# P1001-001-007-320_-_Programmer.net
KiCad netlist of a schematic drawn in EAGLE
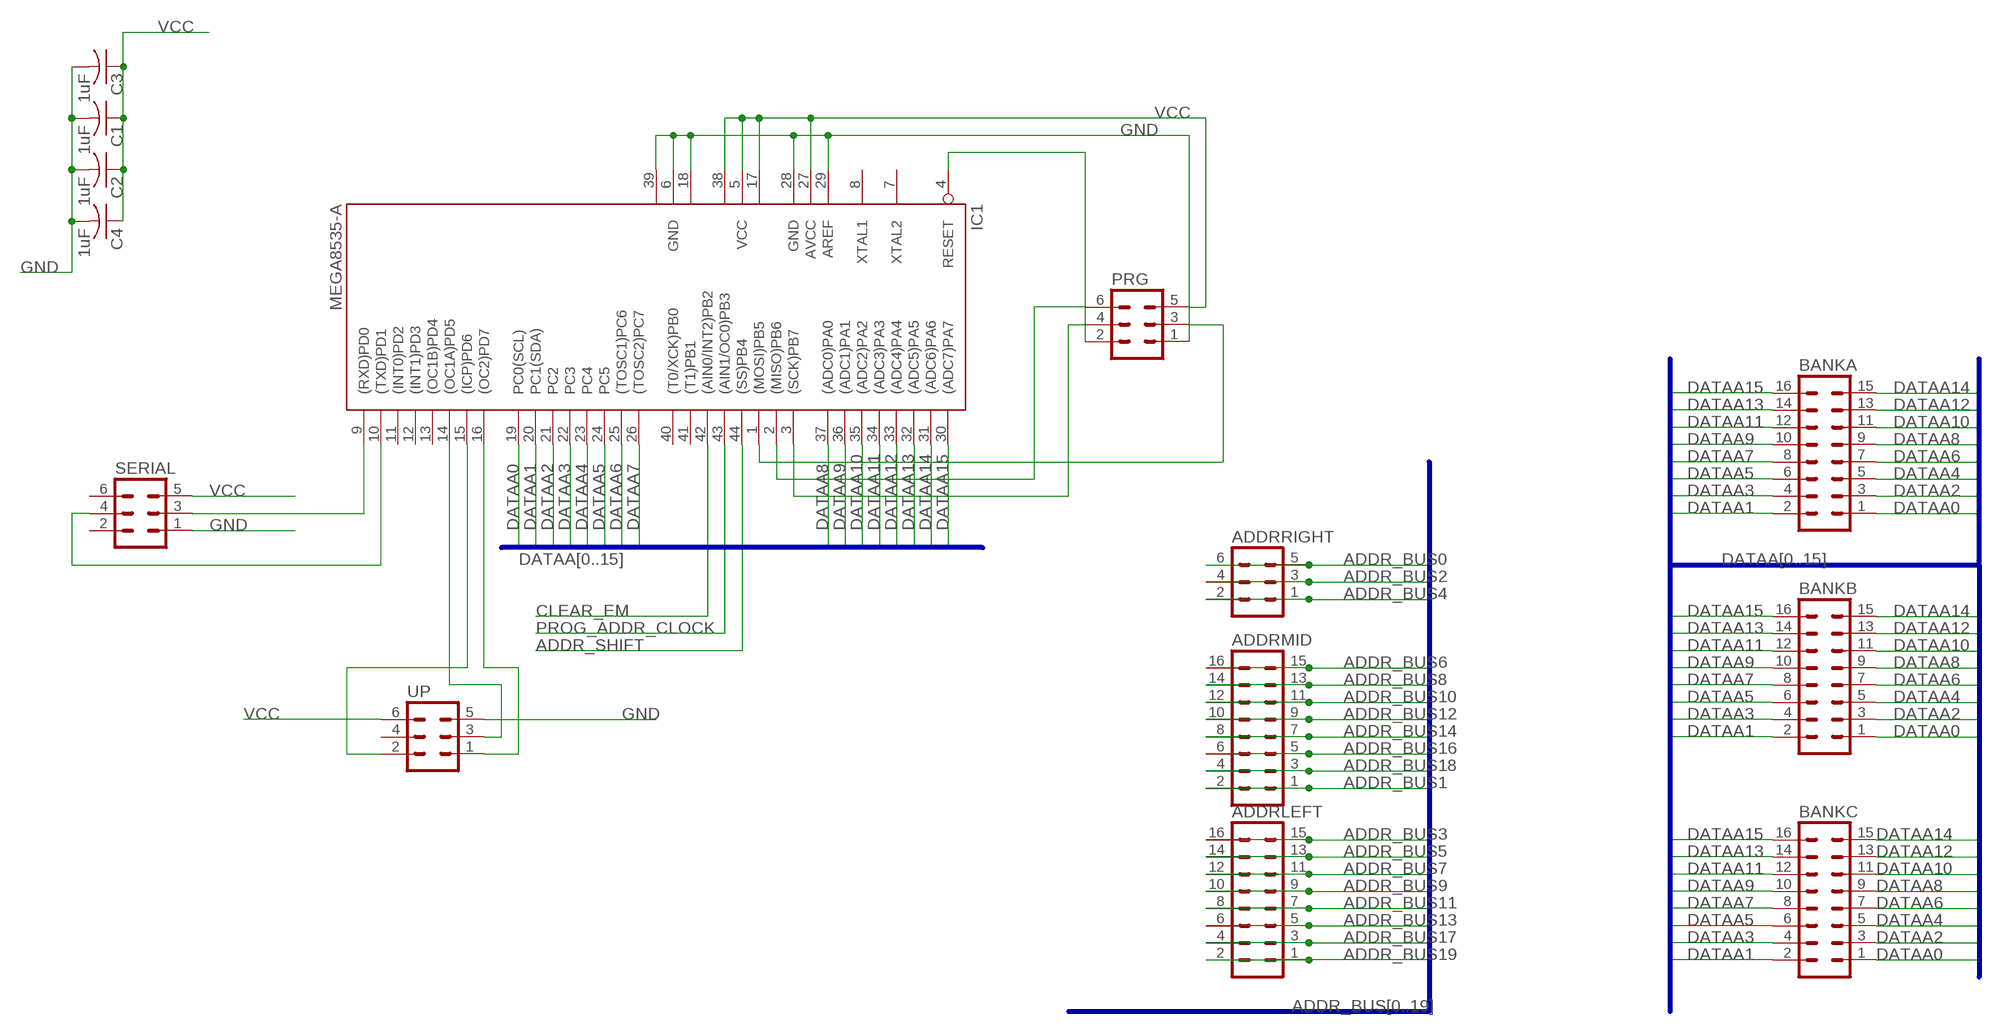
[diagram p0: schematic, sheet 1]
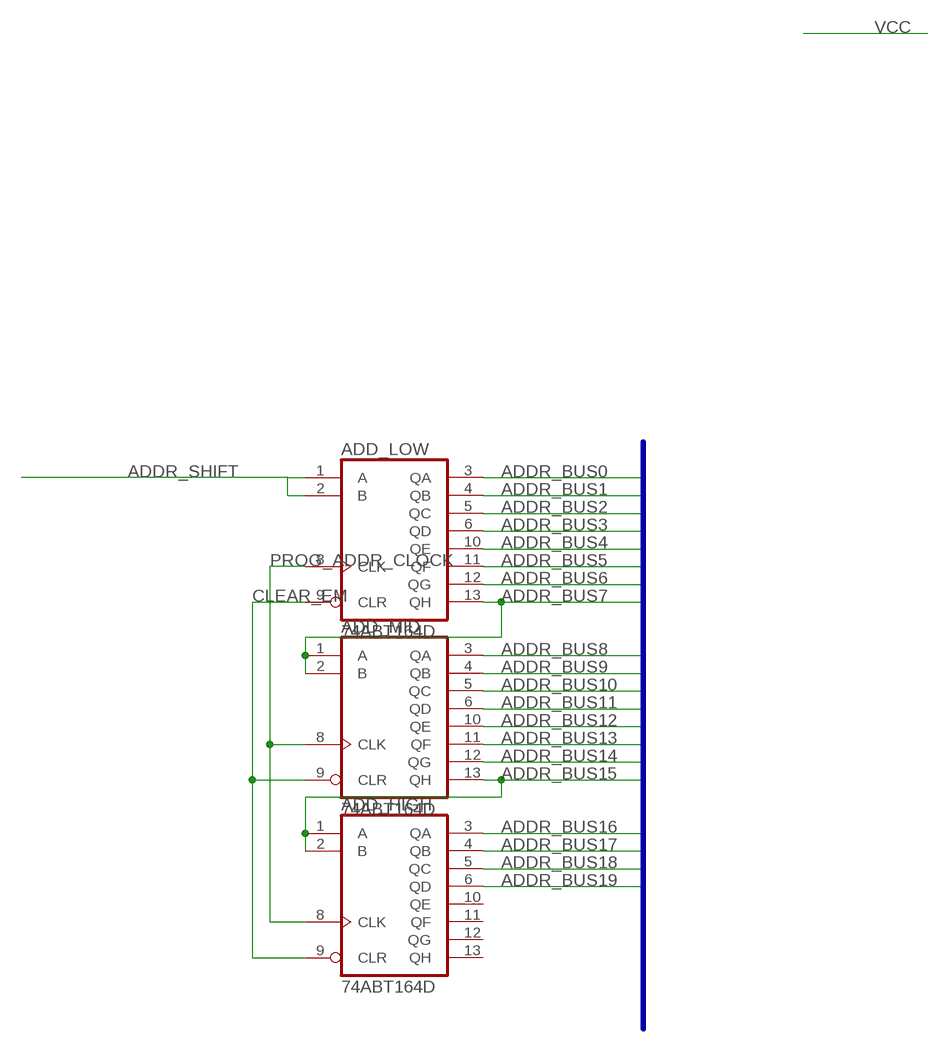
[diagram p1: schematic, sheet 2]

(export (version "E")
  (design (tool "Eeschema 10.0.6"))
  (components
    (comp (ref "ADD_HIGH")
      (value "74ABT164D")
      (footprint "eagle-import:SO14")
      (libsource (lib "eagle-import") (part "74164DABT"))
    )
    (comp (ref "ADD_LOW")
      (value "74ABT164D")
      (footprint "eagle-import:SO14")
      (libsource (lib "eagle-import") (part "74164DABT"))
    )
    (comp (ref "ADD_MID")
      (value "74ABT164D")
      (footprint "eagle-import:SO14")
      (libsource (lib "eagle-import") (part "74164DABT"))
    )
    (comp (ref "ADDRLEFT")
      (value "ML16")
      (footprint "eagle-import:ML16")
      (libsource (lib "eagle-import") (part "ML16"))
    )
    (comp (ref "ADDRMID")
      (value "ML16")
      (footprint "eagle-import:ML16")
      (libsource (lib "eagle-import") (part "ML16"))
    )
    (comp (ref "ADDRRIGHT")
      (value "ML6")
      (footprint "eagle-import:ML6")
      (libsource (lib "eagle-import") (part "ML6"))
    )
    (comp (ref "BANKA")
      (value "ML16")
      (footprint "eagle-import:ML16")
      (libsource (lib "eagle-import") (part "ML16"))
    )
    (comp (ref "BANKB")
      (value "ML16")
      (footprint "eagle-import:ML16")
      (libsource (lib "eagle-import") (part "ML16"))
    )
    (comp (ref "BANKC")
      (value "ML16")
      (footprint "eagle-import:ML16")
      (libsource (lib "eagle-import") (part "ML16"))
    )
    (comp (ref "C1")
      (value "1uF")
      (footprint "eagle-import:C1206")
      (libsource (lib "eagle-import") (part "C-USC1206"))
    )
    (comp (ref "C2")
      (value "1uF")
      (footprint "eagle-import:C1206")
      (libsource (lib "eagle-import") (part "C-USC1206"))
    )
    (comp (ref "C3")
      (value "1uF")
      (footprint "eagle-import:C1206")
      (libsource (lib "eagle-import") (part "C-USC1206"))
    )
    (comp (ref "C4")
      (value "1uF")
      (footprint "eagle-import:C1206")
      (libsource (lib "eagle-import") (part "C-USC1206"))
    )
    (comp (ref "IC1")
      (value "MEGA8535-A")
      (footprint "eagle-import:TQFP44")
      (fields (field (name "MPN") "ATMEGA8535-16AU"))
      (libsource (lib "eagle-import") (part "MEGA8535-A"))
    )
    (comp (ref "PRG")
      (value "ML6")
      (footprint "eagle-import:ML6")
      (libsource (lib "eagle-import") (part "ML6"))
    )
    (comp (ref "SERIAL")
      (value "ML6")
      (footprint "eagle-import:ML6")
      (libsource (lib "eagle-import") (part "ML6"))
    )
    (comp (ref "UP")
      (value "ML6")
      (footprint "eagle-import:ML6")
      (libsource (lib "eagle-import") (part "ML6"))
    )
  )
  (nets
    (net (code "4") (name "ADDR_BUS0") (class "Default")
      (node (ref "ADDRRIGHT") (pin "5") (pinfunction "5_5") (pintype "passive"))
      (node (ref "ADDRRIGHT") (pin "6") (pinfunction "6_6") (pintype "passive"))
      (node (ref "ADD_LOW") (pin "3") (pinfunction "QA_3") (pintype "output"))
    )
    (net (code "5") (name "ADDR_BUS1") (class "Default")
      (node (ref "ADDRMID") (pin "1") (pinfunction "1_1") (pintype "passive"))
      (node (ref "ADDRMID") (pin "2") (pinfunction "2_2") (pintype "passive"))
      (node (ref "ADD_LOW") (pin "4") (pinfunction "QB_4") (pintype "output"))
    )
    (net (code "6") (name "ADDR_BUS2") (class "Default")
      (node (ref "ADDRRIGHT") (pin "3") (pinfunction "3_3") (pintype "passive"))
      (node (ref "ADDRRIGHT") (pin "4") (pinfunction "4_4") (pintype "passive"))
      (node (ref "ADD_LOW") (pin "5") (pinfunction "QC_5") (pintype "output"))
    )
    (net (code "7") (name "ADDR_BUS3") (class "Default")
      (node (ref "ADDRLEFT") (pin "15") (pinfunction "15_15") (pintype "passive"))
      (node (ref "ADDRLEFT") (pin "16") (pinfunction "16_16") (pintype "passive"))
      (node (ref "ADD_LOW") (pin "6") (pinfunction "QD_6") (pintype "output"))
    )
    (net (code "8") (name "ADDR_BUS4") (class "Default")
      (node (ref "ADDRRIGHT") (pin "1") (pinfunction "1_1") (pintype "passive"))
      (node (ref "ADDRRIGHT") (pin "2") (pinfunction "2_2") (pintype "passive"))
      (node (ref "ADD_LOW") (pin "10") (pinfunction "QE_10") (pintype "output"))
    )
    (net (code "9") (name "ADDR_BUS5") (class "Default")
      (node (ref "ADDRLEFT") (pin "13") (pinfunction "13_13") (pintype "passive"))
      (node (ref "ADDRLEFT") (pin "14") (pinfunction "14_14") (pintype "passive"))
      (node (ref "ADD_LOW") (pin "11") (pinfunction "QF_11") (pintype "output"))
    )
    (net (code "10") (name "ADDR_BUS6") (class "Default")
      (node (ref "ADDRMID") (pin "15") (pinfunction "15_15") (pintype "passive"))
      (node (ref "ADDRMID") (pin "16") (pinfunction "16_16") (pintype "passive"))
      (node (ref "ADD_LOW") (pin "12") (pinfunction "QG_12") (pintype "output"))
    )
    (net (code "11") (name "ADDR_BUS7") (class "Default")
      (node (ref "ADDRLEFT") (pin "11") (pinfunction "11_11") (pintype "passive"))
      (node (ref "ADDRLEFT") (pin "12") (pinfunction "12_12") (pintype "passive"))
      (node (ref "ADD_LOW") (pin "13") (pinfunction "QH_13") (pintype "output"))
      (node (ref "ADD_MID") (pin "1") (pinfunction "A_1") (pintype "input"))
      (node (ref "ADD_MID") (pin "2") (pinfunction "B_2") (pintype "input"))
    )
    (net (code "12") (name "ADDR_BUS8") (class "Default")
      (node (ref "ADDRMID") (pin "13") (pinfunction "13_13") (pintype "passive"))
      (node (ref "ADDRMID") (pin "14") (pinfunction "14_14") (pintype "passive"))
      (node (ref "ADD_MID") (pin "3") (pinfunction "QA_3") (pintype "output"))
    )
    (net (code "13") (name "ADDR_BUS9") (class "Default")
      (node (ref "ADDRLEFT") (pin "10") (pinfunction "10_10") (pintype "passive"))
      (node (ref "ADDRLEFT") (pin "9") (pinfunction "9_9") (pintype "passive"))
      (node (ref "ADD_MID") (pin "4") (pinfunction "QB_4") (pintype "output"))
    )
    (net (code "14") (name "ADDR_BUS10") (class "Default")
      (node (ref "ADDRMID") (pin "11") (pinfunction "11_11") (pintype "passive"))
      (node (ref "ADDRMID") (pin "12") (pinfunction "12_12") (pintype "passive"))
      (node (ref "ADD_MID") (pin "5") (pinfunction "QC_5") (pintype "output"))
    )
    (net (code "15") (name "ADDR_BUS11") (class "Default")
      (node (ref "ADDRLEFT") (pin "7") (pinfunction "7_7") (pintype "passive"))
      (node (ref "ADDRLEFT") (pin "8") (pinfunction "8_8") (pintype "passive"))
      (node (ref "ADD_MID") (pin "6") (pinfunction "QD_6") (pintype "output"))
    )
    (net (code "16") (name "ADDR_BUS12") (class "Default")
      (node (ref "ADDRMID") (pin "10") (pinfunction "10_10") (pintype "passive"))
      (node (ref "ADDRMID") (pin "9") (pinfunction "9_9") (pintype "passive"))
      (node (ref "ADD_MID") (pin "10") (pinfunction "QE_10") (pintype "output"))
    )
    (net (code "17") (name "ADDR_BUS13") (class "Default")
      (node (ref "ADDRLEFT") (pin "5") (pinfunction "5_5") (pintype "passive"))
      (node (ref "ADDRLEFT") (pin "6") (pinfunction "6_6") (pintype "passive"))
      (node (ref "ADD_MID") (pin "11") (pinfunction "QF_11") (pintype "output"))
    )
    (net (code "18") (name "ADDR_BUS14") (class "Default")
      (node (ref "ADDRMID") (pin "7") (pinfunction "7_7") (pintype "passive"))
      (node (ref "ADDRMID") (pin "8") (pinfunction "8_8") (pintype "passive"))
      (node (ref "ADD_MID") (pin "12") (pinfunction "QG_12") (pintype "output"))
    )
    (net (code "19") (name "ADDR_BUS15") (class "Default")
      (node (ref "ADD_HIGH") (pin "1") (pinfunction "A_1") (pintype "input"))
      (node (ref "ADD_HIGH") (pin "2") (pinfunction "B_2") (pintype "input"))
      (node (ref "ADD_MID") (pin "13") (pinfunction "QH_13") (pintype "output"))
    )
    (net (code "20") (name "ADDR_BUS16") (class "Default")
      (node (ref "ADDRMID") (pin "5") (pinfunction "5_5") (pintype "passive"))
      (node (ref "ADDRMID") (pin "6") (pinfunction "6_6") (pintype "passive"))
      (node (ref "ADD_HIGH") (pin "3") (pinfunction "QA_3") (pintype "output"))
    )
    (net (code "21") (name "ADDR_BUS17") (class "Default")
      (node (ref "ADDRLEFT") (pin "3") (pinfunction "3_3") (pintype "passive"))
      (node (ref "ADDRLEFT") (pin "4") (pinfunction "4_4") (pintype "passive"))
      (node (ref "ADD_HIGH") (pin "4") (pinfunction "QB_4") (pintype "output"))
    )
    (net (code "22") (name "ADDR_BUS18") (class "Default")
      (node (ref "ADDRMID") (pin "3") (pinfunction "3_3") (pintype "passive"))
      (node (ref "ADDRMID") (pin "4") (pinfunction "4_4") (pintype "passive"))
      (node (ref "ADD_HIGH") (pin "5") (pinfunction "QC_5") (pintype "output"))
    )
    (net (code "23") (name "ADDR_BUS19") (class "Default")
      (node (ref "ADDRLEFT") (pin "1") (pinfunction "1_1") (pintype "passive"))
      (node (ref "ADDRLEFT") (pin "2") (pinfunction "2_2") (pintype "passive"))
      (node (ref "ADD_HIGH") (pin "6") (pinfunction "QD_6") (pintype "output"))
    )
    (net (code "24") (name "ADDR_SHIFT") (class "Default")
      (node (ref "ADD_LOW") (pin "1") (pinfunction "A_1") (pintype "input"))
      (node (ref "ADD_LOW") (pin "2") (pinfunction "B_2") (pintype "input"))
      (node (ref "IC1") (pin "44") (pinfunction "(SS)PB4_44") (pintype "bidirectional"))
    )
    (net (code "25") (name "CLEAR_EM") (class "Default")
      (node (ref "ADD_HIGH") (pin "9") (pinfunction "CLR_9") (pintype "input"))
      (node (ref "ADD_LOW") (pin "9") (pinfunction "CLR_9") (pintype "input"))
      (node (ref "ADD_MID") (pin "9") (pinfunction "CLR_9") (pintype "input"))
      (node (ref "IC1") (pin "42") (pinfunction "(AIN0/INT2)PB2_42") (pintype "bidirectional"))
    )
    (net (code "26") (name "DATAA0") (class "Default")
      (node (ref "BANKA") (pin "1") (pinfunction "1_1") (pintype "passive"))
      (node (ref "BANKB") (pin "1") (pinfunction "1_1") (pintype "passive"))
      (node (ref "BANKC") (pin "1") (pinfunction "1_1") (pintype "passive"))
      (node (ref "IC1") (pin "19") (pinfunction "PC0(SCL)_19") (pintype "bidirectional"))
    )
    (net (code "27") (name "DATAA1") (class "Default")
      (node (ref "BANKA") (pin "2") (pinfunction "2_2") (pintype "passive"))
      (node (ref "BANKB") (pin "2") (pinfunction "2_2") (pintype "passive"))
      (node (ref "BANKC") (pin "2") (pinfunction "2_2") (pintype "passive"))
      (node (ref "IC1") (pin "20") (pinfunction "PC1(SDA)_20") (pintype "bidirectional"))
    )
    (net (code "28") (name "DATAA2") (class "Default")
      (node (ref "BANKA") (pin "3") (pinfunction "3_3") (pintype "passive"))
      (node (ref "BANKB") (pin "3") (pinfunction "3_3") (pintype "passive"))
      (node (ref "BANKC") (pin "3") (pinfunction "3_3") (pintype "passive"))
      (node (ref "IC1") (pin "21") (pinfunction "PC2_21") (pintype "bidirectional"))
    )
    (net (code "29") (name "DATAA3") (class "Default")
      (node (ref "BANKA") (pin "4") (pinfunction "4_4") (pintype "passive"))
      (node (ref "BANKB") (pin "4") (pinfunction "4_4") (pintype "passive"))
      (node (ref "BANKC") (pin "4") (pinfunction "4_4") (pintype "passive"))
      (node (ref "IC1") (pin "22") (pinfunction "PC3_22") (pintype "bidirectional"))
    )
    (net (code "30") (name "DATAA4") (class "Default")
      (node (ref "BANKA") (pin "5") (pinfunction "5_5") (pintype "passive"))
      (node (ref "BANKB") (pin "5") (pinfunction "5_5") (pintype "passive"))
      (node (ref "BANKC") (pin "5") (pinfunction "5_5") (pintype "passive"))
      (node (ref "IC1") (pin "23") (pinfunction "PC4_23") (pintype "bidirectional"))
    )
    (net (code "31") (name "DATAA5") (class "Default")
      (node (ref "BANKA") (pin "6") (pinfunction "6_6") (pintype "passive"))
      (node (ref "BANKB") (pin "6") (pinfunction "6_6") (pintype "passive"))
      (node (ref "BANKC") (pin "6") (pinfunction "6_6") (pintype "passive"))
      (node (ref "IC1") (pin "24") (pinfunction "PC5_24") (pintype "bidirectional"))
    )
    (net (code "32") (name "DATAA6") (class "Default")
      (node (ref "BANKA") (pin "7") (pinfunction "7_7") (pintype "passive"))
      (node (ref "BANKB") (pin "7") (pinfunction "7_7") (pintype "passive"))
      (node (ref "BANKC") (pin "7") (pinfunction "7_7") (pintype "passive"))
      (node (ref "IC1") (pin "25") (pinfunction "(TOSC1)PC6_25") (pintype "bidirectional"))
    )
    (net (code "33") (name "DATAA7") (class "Default")
      (node (ref "BANKA") (pin "8") (pinfunction "8_8") (pintype "passive"))
      (node (ref "BANKB") (pin "8") (pinfunction "8_8") (pintype "passive"))
      (node (ref "BANKC") (pin "8") (pinfunction "8_8") (pintype "passive"))
      (node (ref "IC1") (pin "26") (pinfunction "(TOSC2)PC7_26") (pintype "bidirectional"))
    )
    (net (code "34") (name "DATAA8") (class "Default")
      (node (ref "BANKA") (pin "9") (pinfunction "9_9") (pintype "passive"))
      (node (ref "BANKB") (pin "9") (pinfunction "9_9") (pintype "passive"))
      (node (ref "BANKC") (pin "9") (pinfunction "9_9") (pintype "passive"))
      (node (ref "IC1") (pin "37") (pinfunction "(ADC0)PA0_37") (pintype "bidirectional"))
    )
    (net (code "35") (name "DATAA9") (class "Default")
      (node (ref "BANKA") (pin "10") (pinfunction "10_10") (pintype "passive"))
      (node (ref "BANKB") (pin "10") (pinfunction "10_10") (pintype "passive"))
      (node (ref "BANKC") (pin "10") (pinfunction "10_10") (pintype "passive"))
      (node (ref "IC1") (pin "36") (pinfunction "(ADC1)PA1_36") (pintype "bidirectional"))
    )
    (net (code "36") (name "DATAA10") (class "Default")
      (node (ref "BANKA") (pin "11") (pinfunction "11_11") (pintype "passive"))
      (node (ref "BANKB") (pin "11") (pinfunction "11_11") (pintype "passive"))
      (node (ref "BANKC") (pin "11") (pinfunction "11_11") (pintype "passive"))
      (node (ref "IC1") (pin "35") (pinfunction "(ADC2)PA2_35") (pintype "bidirectional"))
    )
    (net (code "37") (name "DATAA11") (class "Default")
      (node (ref "BANKA") (pin "12") (pinfunction "12_12") (pintype "passive"))
      (node (ref "BANKB") (pin "12") (pinfunction "12_12") (pintype "passive"))
      (node (ref "BANKC") (pin "12") (pinfunction "12_12") (pintype "passive"))
      (node (ref "IC1") (pin "34") (pinfunction "(ADC3)PA3_34") (pintype "bidirectional"))
    )
    (net (code "38") (name "DATAA12") (class "Default")
      (node (ref "BANKA") (pin "13") (pinfunction "13_13") (pintype "passive"))
      (node (ref "BANKB") (pin "13") (pinfunction "13_13") (pintype "passive"))
      (node (ref "BANKC") (pin "13") (pinfunction "13_13") (pintype "passive"))
      (node (ref "IC1") (pin "33") (pinfunction "(ADC4)PA4_33") (pintype "bidirectional"))
    )
    (net (code "39") (name "DATAA13") (class "Default")
      (node (ref "BANKA") (pin "14") (pinfunction "14_14") (pintype "passive"))
      (node (ref "BANKB") (pin "14") (pinfunction "14_14") (pintype "passive"))
      (node (ref "BANKC") (pin "14") (pinfunction "14_14") (pintype "passive"))
      (node (ref "IC1") (pin "32") (pinfunction "(ADC5)PA5_32") (pintype "bidirectional"))
    )
    (net (code "40") (name "DATAA14") (class "Default")
      (node (ref "BANKA") (pin "15") (pinfunction "15_15") (pintype "passive"))
      (node (ref "BANKB") (pin "15") (pinfunction "15_15") (pintype "passive"))
      (node (ref "BANKC") (pin "15") (pinfunction "15_15") (pintype "passive"))
      (node (ref "IC1") (pin "31") (pinfunction "(ADC6)PA6_31") (pintype "bidirectional"))
    )
    (net (code "41") (name "DATAA15") (class "Default")
      (node (ref "BANKA") (pin "16") (pinfunction "16_16") (pintype "passive"))
      (node (ref "BANKB") (pin "16") (pinfunction "16_16") (pintype "passive"))
      (node (ref "BANKC") (pin "16") (pinfunction "16_16") (pintype "passive"))
      (node (ref "IC1") (pin "30") (pinfunction "(ADC7)PA7_30") (pintype "bidirectional"))
    )
    (net (code "42") (name "GND") (class "Default")
      (node (ref "C1") (pin "2") (pinfunction "2_2") (pintype "passive"))
      (node (ref "C2") (pin "2") (pinfunction "2_2") (pintype "passive"))
      (node (ref "C3") (pin "2") (pinfunction "2_2") (pintype "passive"))
      (node (ref "C4") (pin "2") (pinfunction "2_2") (pintype "passive"))
      (node (ref "IC1") (pin "18") (pinfunction "GND1_18") (pintype "power_in"))
      (node (ref "IC1") (pin "28") (pinfunction "GND_28") (pintype "power_in"))
      (node (ref "IC1") (pin "29") (pinfunction "AREF_29") (pintype "passive"))
      (node (ref "IC1") (pin "39") (pinfunction "GND2_39") (pintype "power_in"))
      (node (ref "IC1") (pin "6") (pinfunction "GND_6") (pintype "power_in"))
      (node (ref "PRG") (pin "1") (pinfunction "1_1") (pintype "passive"))
      (node (ref "SERIAL") (pin "1") (pinfunction "1_1") (pintype "passive"))
      (node (ref "UP") (pin "5") (pinfunction "5_5") (pintype "passive"))
    )
    (net (code "43") (name "Net-(IC1-(ICP)PD6)") (class "Default")
      (node (ref "IC1") (pin "15") (pinfunction "(ICP)PD6_15") (pintype "bidirectional"))
      (node (ref "UP") (pin "2") (pinfunction "2_2") (pintype "passive"))
    )
    (net (code "44") (name "Net-(IC1-(MISO)PB6)") (class "Default")
      (node (ref "IC1") (pin "2") (pinfunction "(MISO)PB6_2") (pintype "bidirectional"))
      (node (ref "PRG") (pin "6") (pinfunction "6_6") (pintype "passive"))
    )
    (net (code "45") (name "Net-(IC1-(MOSI)PB5)") (class "Default")
      (node (ref "IC1") (pin "1") (pinfunction "(MOSI)PB5_1") (pintype "bidirectional"))
      (node (ref "PRG") (pin "3") (pinfunction "3_3") (pintype "passive"))
    )
    (net (code "46") (name "Net-(IC1-(OC1A)PD5)") (class "Default")
      (node (ref "IC1") (pin "14") (pinfunction "(OC1A)PD5_14") (pintype "bidirectional"))
      (node (ref "UP") (pin "3") (pinfunction "3_3") (pintype "passive"))
    )
    (net (code "47") (name "Net-(IC1-(OC2)PD7)") (class "Default")
      (node (ref "IC1") (pin "16") (pinfunction "(OC2)PD7_16") (pintype "bidirectional"))
      (node (ref "UP") (pin "1") (pinfunction "1_1") (pintype "passive"))
    )
    (net (code "48") (name "Net-(IC1-(RXD)PD0)") (class "Default")
      (node (ref "IC1") (pin "9") (pinfunction "(RXD)PD0_9") (pintype "bidirectional"))
      (node (ref "SERIAL") (pin "3") (pinfunction "3_3") (pintype "passive"))
    )
    (net (code "49") (name "Net-(IC1-(SCK)PB7)") (class "Default")
      (node (ref "IC1") (pin "3") (pinfunction "(SCK)PB7_3") (pintype "bidirectional"))
      (node (ref "PRG") (pin "4") (pinfunction "4_4") (pintype "passive"))
    )
    (net (code "50") (name "Net-(IC1-(TXD)PD1)") (class "Default")
      (node (ref "IC1") (pin "10") (pinfunction "(TXD)PD1_10") (pintype "bidirectional"))
      (node (ref "SERIAL") (pin "4") (pinfunction "4_4") (pintype "passive"))
    )
    (net (code "51") (name "Net-(IC1-RESET)") (class "Default")
      (node (ref "IC1") (pin "4") (pinfunction "RESET_4") (pintype "input"))
      (node (ref "PRG") (pin "2") (pinfunction "2_2") (pintype "passive"))
    )
    (net (code "52") (name "PROG_ADDR_CLOCK") (class "Default")
      (node (ref "ADD_HIGH") (pin "8") (pinfunction "CLK_8") (pintype "input"))
      (node (ref "ADD_LOW") (pin "8") (pinfunction "CLK_8") (pintype "input"))
      (node (ref "ADD_MID") (pin "8") (pinfunction "CLK_8") (pintype "input"))
      (node (ref "IC1") (pin "43") (pinfunction "(AIN1/OC0)PB3_43") (pintype "bidirectional"))
    )
    (net (code "53") (name "VCC") (class "Default")
      (node (ref "C1") (pin "1") (pinfunction "1_1") (pintype "passive"))
      (node (ref "C2") (pin "1") (pinfunction "1_1") (pintype "passive"))
      (node (ref "C3") (pin "1") (pinfunction "1_1") (pintype "passive"))
      (node (ref "C4") (pin "1") (pinfunction "1_1") (pintype "passive"))
      (node (ref "IC1") (pin "17") (pinfunction "VCC1_17") (pintype "power_in"))
      (node (ref "IC1") (pin "27") (pinfunction "AVCC_27") (pintype "power_in"))
      (node (ref "IC1") (pin "38") (pinfunction "VCC2_38") (pintype "power_in"))
      (node (ref "IC1") (pin "5") (pinfunction "VCC_5") (pintype "power_in"))
      (node (ref "PRG") (pin "5") (pinfunction "5_5") (pintype "passive"))
      (node (ref "SERIAL") (pin "5") (pinfunction "5_5") (pintype "passive"))
      (node (ref "UP") (pin "6") (pinfunction "6_6") (pintype "passive"))
    )
    (net (code "54") (name "unconnected-(ADD_HIGHA-QE-Pad10)") (class "Default")
      (node (ref "ADD_HIGH") (pin "10") (pinfunction "QE_10") (pintype "output"))
    )
    (net (code "55") (name "unconnected-(ADD_HIGHA-QF-Pad11)") (class "Default")
      (node (ref "ADD_HIGH") (pin "11") (pinfunction "QF_11") (pintype "output"))
    )
    (net (code "56") (name "unconnected-(ADD_HIGHA-QG-Pad12)") (class "Default")
      (node (ref "ADD_HIGH") (pin "12") (pinfunction "QG_12") (pintype "output"))
    )
    (net (code "57") (name "unconnected-(ADD_HIGHA-QH-Pad13)") (class "Default")
      (node (ref "ADD_HIGH") (pin "13") (pinfunction "QH_13") (pintype "output"))
    )
    (net (code "58") (name "unconnected-(IC1-(INT0)PD2-Pad11)") (class "Default")
      (node (ref "IC1") (pin "11") (pinfunction "(INT0)PD2_11") (pintype "bidirectional"))
    )
    (net (code "59") (name "unconnected-(IC1-(INT1)PD3-Pad12)") (class "Default")
      (node (ref "IC1") (pin "12") (pinfunction "(INT1)PD3_12") (pintype "bidirectional"))
    )
    (net (code "60") (name "unconnected-(IC1-(OC1B)PD4-Pad13)") (class "Default")
      (node (ref "IC1") (pin "13") (pinfunction "(OC1B)PD4_13") (pintype "bidirectional"))
    )
    (net (code "61") (name "unconnected-(IC1-(T0{slash}XCK)PB0-Pad40)") (class "Default")
      (node (ref "IC1") (pin "40") (pinfunction "(T0/XCK)PB0_40") (pintype "bidirectional"))
    )
    (net (code "62") (name "unconnected-(IC1-(T1)PB1-Pad41)") (class "Default")
      (node (ref "IC1") (pin "41") (pinfunction "(T1)PB1_41") (pintype "bidirectional"))
    )
    (net (code "63") (name "unconnected-(IC1-XTAL1-Pad8)") (class "Default")
      (node (ref "IC1") (pin "8") (pinfunction "XTAL1_8") (pintype "bidirectional"))
    )
    (net (code "64") (name "unconnected-(IC1-XTAL2-Pad7)") (class "Default")
      (node (ref "IC1") (pin "7") (pinfunction "XTAL2_7") (pintype "bidirectional"))
    )
    (net (code "65") (name "unconnected-(SERIAL-Pad2)") (class "Default")
      (node (ref "SERIAL") (pin "2") (pinfunction "2_2") (pintype "passive"))
    )
    (net (code "66") (name "unconnected-(SERIAL-Pad6)") (class "Default")
      (node (ref "SERIAL") (pin "6") (pinfunction "6_6") (pintype "passive"))
    )
    (net (code "67") (name "unconnected-(UP-Pad4)") (class "Default")
      (node (ref "UP") (pin "4") (pinfunction "4_4") (pintype "passive"))
    )
  )
)
